# Personal_Project_2020-21.net
KiCad netlist of a schematic drawn in EasyEDA
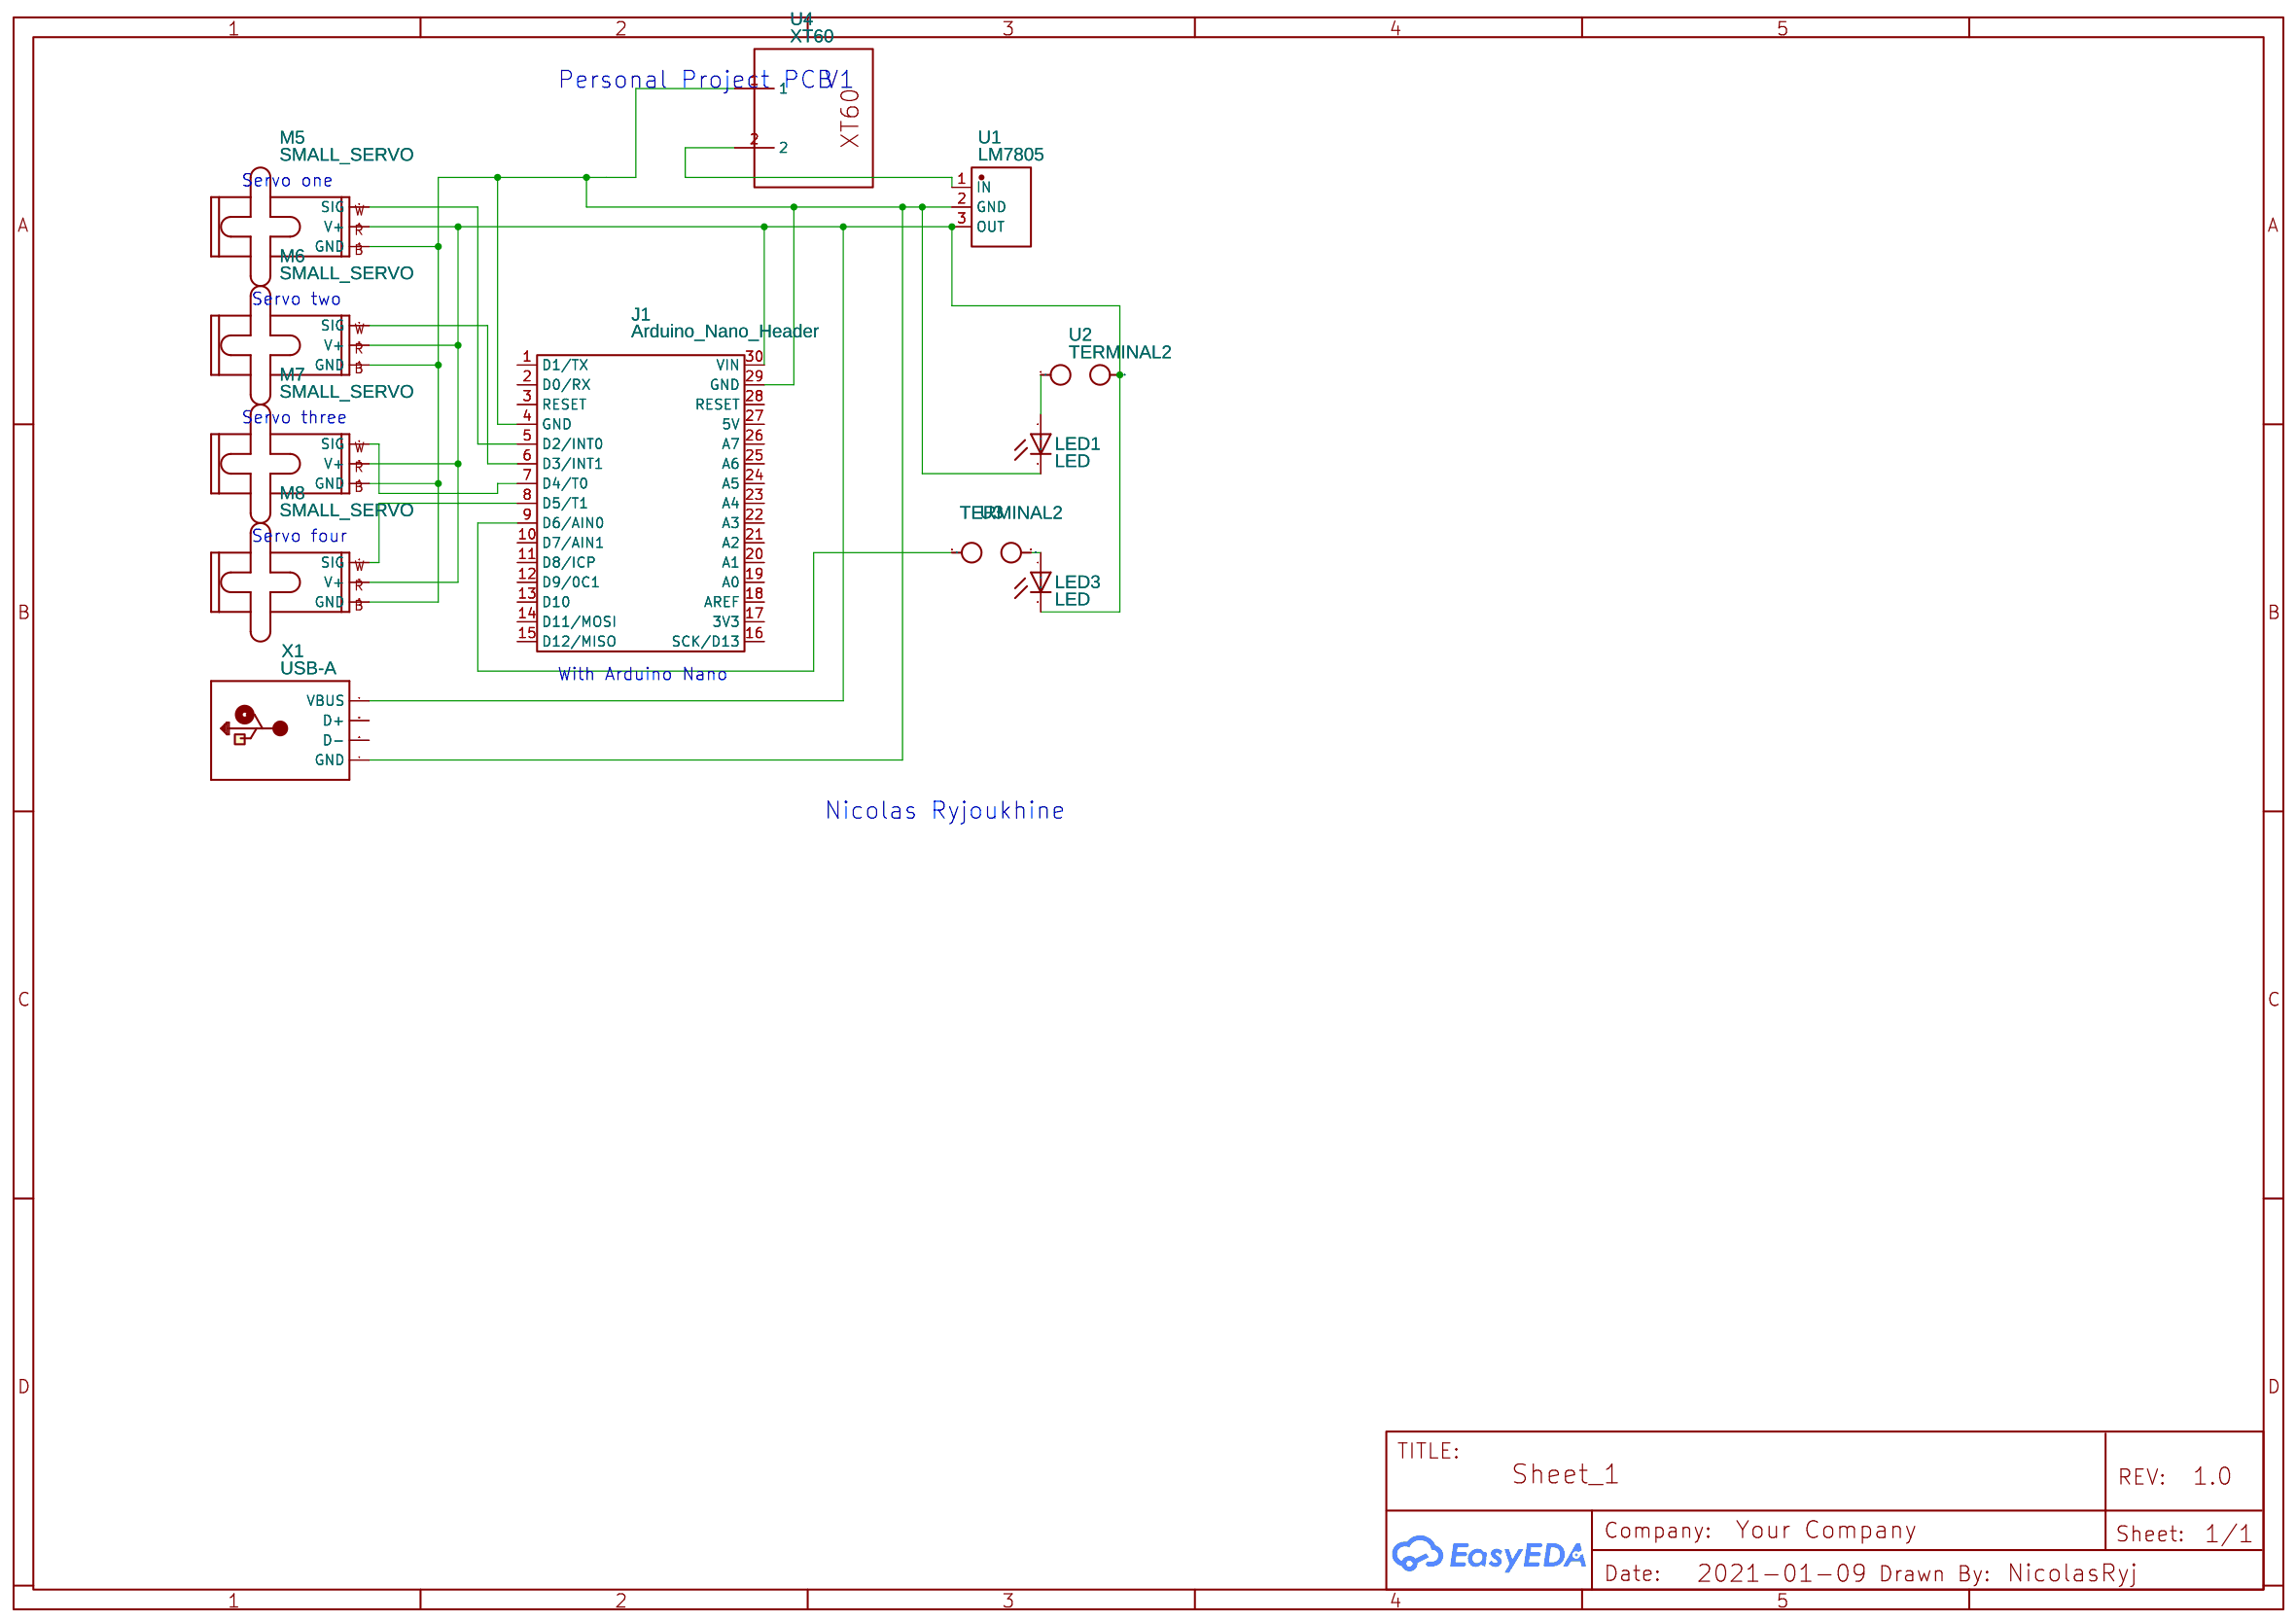
[diagram p0: schematic sheet]

(export (version "E")
  (design (tool "Eeschema 10.0.6"))
  (components
    (comp (ref "J1") (value "Arduino_Nano_Header") (libsource (lib "") (part "Arduino_Nano_Header")))
    (comp (ref "LED1") (value "LED") (libsource (lib "") (part "LED")))
    (comp (ref "LED3") (value "LED") (libsource (lib "") (part "LED")))
    (comp (ref "M5") (value "SMALL_SERVO") (libsource (lib "") (part "SMALL_SERVO")))
    (comp (ref "M6") (value "SMALL_SERVO") (libsource (lib "") (part "SMALL_SERVO")))
    (comp (ref "M7") (value "SMALL_SERVO") (libsource (lib "") (part "SMALL_SERVO")))
    (comp (ref "M8") (value "SMALL_SERVO") (libsource (lib "") (part "SMALL_SERVO")))
    (comp (ref "U1")
      (value "LM7805")
      (fields (field (name "BOM_Supplier Part") "C845394"))
      (libsource (lib "") (part "LM7805"))
    )
    (comp (ref "U2") (value "TERMINAL2") (libsource (lib "") (part "TERMINAL2")))
    (comp (ref "U3") (value "TERMINAL2") (libsource (lib "") (part "TERMINAL2")))
    (comp (ref "U4") (value "XT60") (libsource (lib "") (part "XT60")))
    (comp (ref "X1") (value "USB-A") (libsource (lib "") (part "USB-A")))
  )
  (nets
    (net (code "1") (name "Net-(J1-D2{slash}INT0)") (class "Default")
      (node (ref "J1") (pin "5") (pinfunction "D2/INT0_5") (pintype "unspecified"))
      (node (ref "M5") (pin "1") (pinfunction "SIG_1") (pintype "unspecified"))
    )
    (net (code "2") (name "Net-(J1-D3{slash}INT1)") (class "Default")
      (node (ref "J1") (pin "6") (pinfunction "D3/INT1_6") (pintype "unspecified"))
      (node (ref "M6") (pin "1") (pinfunction "SIG_1") (pintype "unspecified"))
    )
    (net (code "3") (name "Net-(J1-D4{slash}T0)") (class "Default")
      (node (ref "J1") (pin "7") (pinfunction "D4/T0_7") (pintype "unspecified"))
      (node (ref "M7") (pin "1") (pinfunction "SIG_1") (pintype "unspecified"))
    )
    (net (code "4") (name "Net-(J1-D5{slash}T1)") (class "Default")
      (node (ref "J1") (pin "8") (pinfunction "D5/T1_8") (pintype "unspecified"))
      (node (ref "M8") (pin "1") (pinfunction "SIG_1") (pintype "unspecified"))
    )
    (net (code "5") (name "Net-(J1-D6{slash}AIN0)") (class "Default")
      (node (ref "J1") (pin "9") (pinfunction "D6/AIN0_9") (pintype "unspecified"))
      (node (ref "U3") (pin "1") (pinfunction "1_1") (pintype "unspecified"))
    )
    (net (code "6") (name "Net-(J1-VIN)") (class "Default")
      (node (ref "J1") (pin "30") (pinfunction "VIN_30") (pintype "unspecified"))
      (node (ref "LED3") (pin "K") (pinfunction "C_K") (pintype "unspecified"))
      (node (ref "M5") (pin "2") (pinfunction "V+_2") (pintype "unspecified"))
      (node (ref "M6") (pin "2") (pinfunction "V+_2") (pintype "unspecified"))
      (node (ref "M7") (pin "2") (pinfunction "V+_2") (pintype "unspecified"))
      (node (ref "M8") (pin "2") (pinfunction "V+_2") (pintype "unspecified"))
      (node (ref "U1") (pin "3") (pinfunction "OUT_3") (pintype "unspecified"))
      (node (ref "U2") (pin "2") (pinfunction "2_2") (pintype "unspecified"))
      (node (ref "X1") (pin "1") (pinfunction "VBUS_1") (pintype "passive"))
    )
    (net (code "7") (name "Net-(LED1-C)") (class "Default")
      (node (ref "J1") (pin "29") (pinfunction "GND_29") (pintype "unspecified"))
      (node (ref "J1") (pin "4") (pinfunction "GND_4") (pintype "unspecified"))
      (node (ref "LED1") (pin "K") (pinfunction "C_K") (pintype "unspecified"))
      (node (ref "M5") (pin "3") (pinfunction "GND_3") (pintype "unspecified"))
      (node (ref "M6") (pin "3") (pinfunction "GND_3") (pintype "unspecified"))
      (node (ref "M7") (pin "3") (pinfunction "GND_3") (pintype "unspecified"))
      (node (ref "M8") (pin "3") (pinfunction "GND_3") (pintype "unspecified"))
      (node (ref "U1") (pin "2") (pinfunction "GND_2") (pintype "unspecified"))
      (node (ref "U4") (pin "1") (pinfunction "1_1") (pintype "unspecified"))
      (node (ref "X1") (pin "4") (pinfunction "GND_4") (pintype "passive"))
    )
    (net (code "8") (name "Net-(LED1-PadA)") (class "Default")
      (node (ref "LED1") (pin "A") (pinfunction "A_A") (pintype "unspecified"))
      (node (ref "U2") (pin "1") (pinfunction "1_1") (pintype "unspecified"))
    )
    (net (code "9") (name "Net-(LED3-PadA)") (class "Default")
      (node (ref "LED3") (pin "A") (pinfunction "A_A") (pintype "unspecified"))
      (node (ref "U3") (pin "2") (pinfunction "2_2") (pintype "unspecified"))
    )
    (net (code "10") (name "Net-(U1-IN)") (class "Default")
      (node (ref "U1") (pin "1") (pinfunction "IN_1") (pintype "unspecified"))
      (node (ref "U4") (pin "2") (pinfunction "2_2") (pintype "unspecified"))
    )
    (net (code "11") (name "unconnected-(J1-3V3-Pad17)") (class "Default")
      (node (ref "J1") (pin "17") (pinfunction "3V3_17") (pintype "unspecified"))
    )
    (net (code "12") (name "unconnected-(J1-5V-Pad27)") (class "Default")
      (node (ref "J1") (pin "27") (pinfunction "5V_27") (pintype "unspecified"))
    )
    (net (code "13") (name "unconnected-(J1-A0-Pad19)") (class "Default")
      (node (ref "J1") (pin "19") (pinfunction "A0_19") (pintype "unspecified"))
    )
    (net (code "14") (name "unconnected-(J1-A1-Pad20)") (class "Default")
      (node (ref "J1") (pin "20") (pinfunction "A1_20") (pintype "unspecified"))
    )
    (net (code "15") (name "unconnected-(J1-A2-Pad21)") (class "Default")
      (node (ref "J1") (pin "21") (pinfunction "A2_21") (pintype "unspecified"))
    )
    (net (code "16") (name "unconnected-(J1-A3-Pad22)") (class "Default")
      (node (ref "J1") (pin "22") (pinfunction "A3_22") (pintype "unspecified"))
    )
    (net (code "17") (name "unconnected-(J1-A4-Pad23)") (class "Default")
      (node (ref "J1") (pin "23") (pinfunction "A4_23") (pintype "unspecified"))
    )
    (net (code "18") (name "unconnected-(J1-A5-Pad24)") (class "Default")
      (node (ref "J1") (pin "24") (pinfunction "A5_24") (pintype "unspecified"))
    )
    (net (code "19") (name "unconnected-(J1-A6-Pad25)") (class "Default")
      (node (ref "J1") (pin "25") (pinfunction "A6_25") (pintype "unspecified"))
    )
    (net (code "20") (name "unconnected-(J1-A7-Pad26)") (class "Default")
      (node (ref "J1") (pin "26") (pinfunction "A7_26") (pintype "unspecified"))
    )
    (net (code "21") (name "unconnected-(J1-AREF-Pad18)") (class "Default")
      (node (ref "J1") (pin "18") (pinfunction "AREF_18") (pintype "unspecified"))
    )
    (net (code "22") (name "unconnected-(J1-D0{slash}RX-Pad2)") (class "Default")
      (node (ref "J1") (pin "2") (pinfunction "D0/RX_2") (pintype "unspecified"))
    )
    (net (code "23") (name "unconnected-(J1-D1{slash}TX-Pad1)") (class "Default")
      (node (ref "J1") (pin "1") (pinfunction "D1/TX_1") (pintype "unspecified"))
    )
    (net (code "24") (name "unconnected-(J1-D7{slash}AIN1-Pad10)") (class "Default")
      (node (ref "J1") (pin "10") (pinfunction "D7/AIN1_10") (pintype "unspecified"))
    )
    (net (code "25") (name "unconnected-(J1-D8{slash}ICP-Pad11)") (class "Default")
      (node (ref "J1") (pin "11") (pinfunction "D8/ICP_11") (pintype "unspecified"))
    )
    (net (code "26") (name "unconnected-(J1-D9{slash}0C1-Pad12)") (class "Default")
      (node (ref "J1") (pin "12") (pinfunction "D9/0C1_12") (pintype "unspecified"))
    )
    (net (code "27") (name "unconnected-(J1-D10-Pad13)") (class "Default")
      (node (ref "J1") (pin "13") (pinfunction "D10_13") (pintype "unspecified"))
    )
    (net (code "28") (name "unconnected-(J1-D11{slash}MOSI-Pad14)") (class "Default")
      (node (ref "J1") (pin "14") (pinfunction "D11/MOSI_14") (pintype "unspecified"))
    )
    (net (code "29") (name "unconnected-(J1-D12{slash}MISO-Pad15)") (class "Default")
      (node (ref "J1") (pin "15") (pinfunction "D12/MISO_15") (pintype "unspecified"))
    )
    (net (code "30") (name "unconnected-(J1-RESET-Pad3)") (class "Default")
      (node (ref "J1") (pin "3") (pinfunction "RESET_3") (pintype "unspecified"))
    )
    (net (code "31") (name "unconnected-(J1-RESET-Pad28)") (class "Default")
      (node (ref "J1") (pin "28") (pinfunction "RESET_28") (pintype "unspecified"))
    )
    (net (code "32") (name "unconnected-(J1-SCK{slash}D13-Pad16)") (class "Default")
      (node (ref "J1") (pin "16") (pinfunction "SCK/D13_16") (pintype "unspecified"))
    )
    (net (code "33") (name "unconnected-(X1-D+-Pad3)") (class "Default")
      (node (ref "X1") (pin "3") (pinfunction "D+_3") (pintype "unspecified"))
    )
    (net (code "34") (name "unconnected-(X1-D--Pad2)") (class "Default")
      (node (ref "X1") (pin "2") (pinfunction "D-_2") (pintype "unspecified"))
    )
  )
)
